# Sheet1.net
KiCad netlist of a schematic drawn in Altium Designer
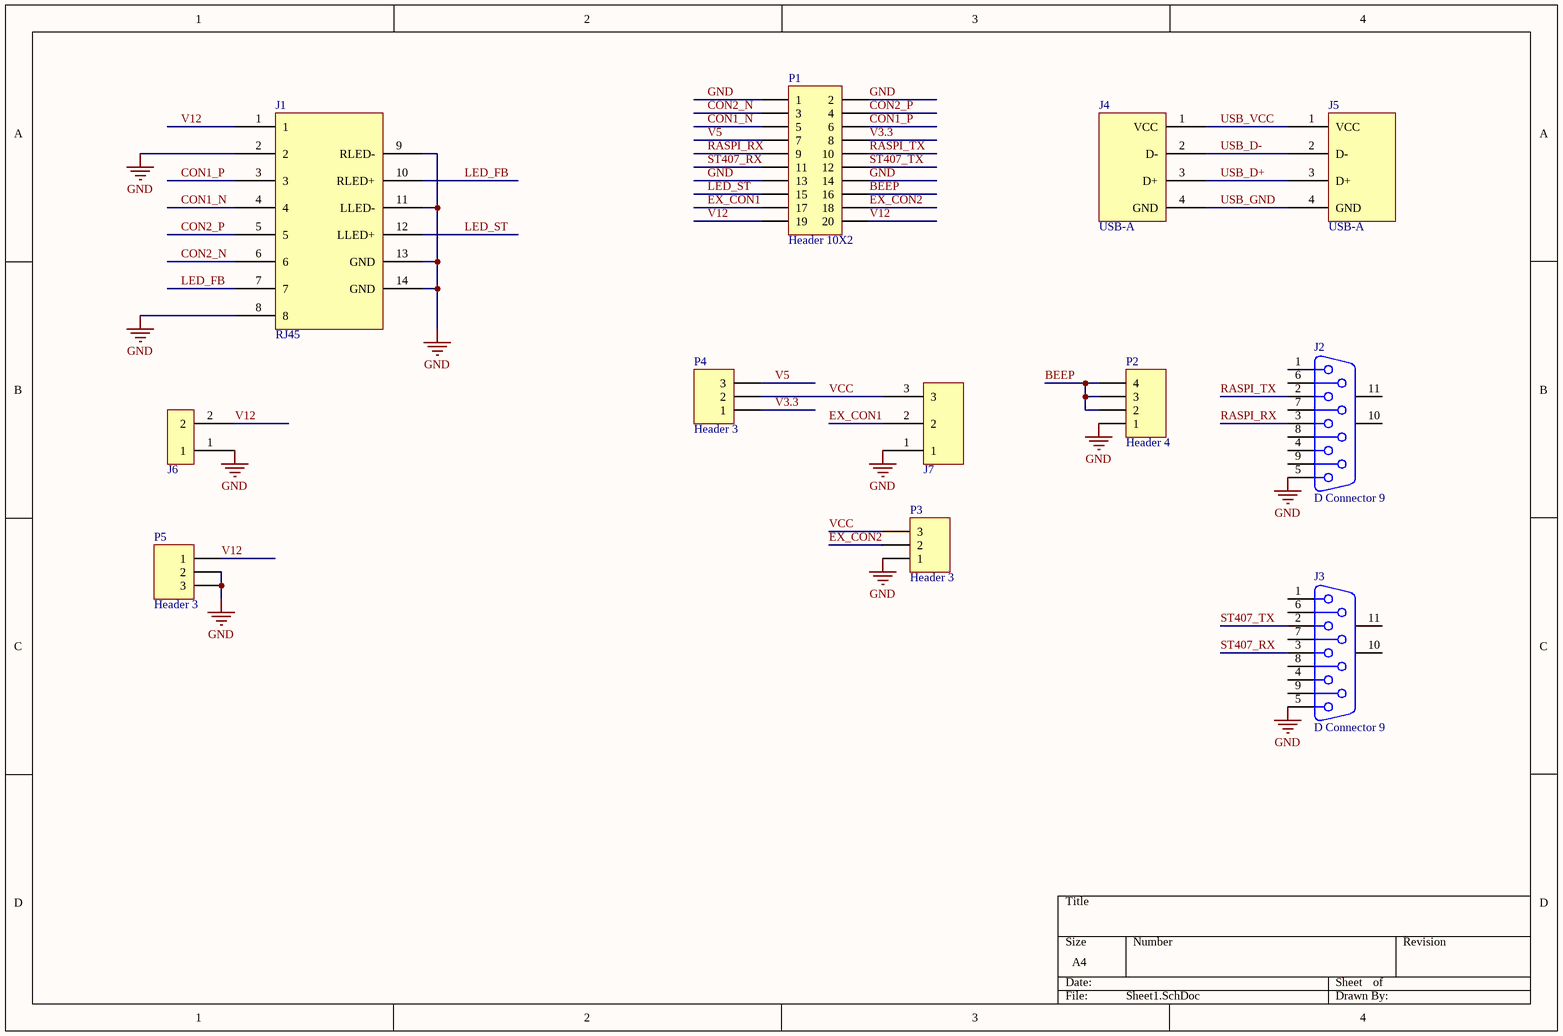
[diagram p0: Sheet1.SchDoc]

(export (version "E")
  (design (tool "Eeschema 10.0.6"))
  (components
    (comp (ref "J1") (value "RJ45") (footprint "RJ45_1") (libsource (lib "CHK-I") (part "RJ45_1")))
    (comp (ref "J2")
      (value "D Connector 9")
      (footprint "DSUB1.385-2H9")
      (description "Receptacle Assembly, 9 Position, Right Angle")
      (fields (field (name "PUBLISHER") "Altium Limited"))
      (libsource (lib "Miscellaneous Connectors") (part "D Connector 9"))
    )
    (comp (ref "J3")
      (value "D Connector 9")
      (footprint "DSUB1.385-2H9")
      (description "Receptacle Assembly, 9 Position, Right Angle")
      (fields (field (name "PUBLISHER") "Altium Limited"))
      (libsource (lib "Miscellaneous Connectors") (part "D Connector 9"))
    )
    (comp (ref "J4")
      (value "USB-A")
      (footprint "USB-A")
      (description "USB-A female")
      (libsource (lib "") (part "USB-A_1"))
    )
    (comp (ref "J5")
      (value "USB-A")
      (footprint "USB-A")
      (description "USB-A female")
      (libsource (lib "CHK-I") (part "USB-A"))
    )
    (comp (ref "J6") (value "XK7.62-2P") (footprint "XK7.62-2P") (libsource (lib "CHK-I") (part "XK7.62-2P")))
    (comp (ref "J7") (value "KF301-3P") (footprint "KF301-3P") (libsource (lib "CHK-I") (part "KF301-3P")))
    (comp (ref "P1")
      (value "Header 10X2")
      (footprint "HDR2X10")
      (description "Header, 10-Pin, Dual row")
      (fields (field (name "PUBLISHER") "Altium Limited"))
      (libsource (lib "Miscellaneous Connectors") (part "Header 10X2"))
    )
    (comp (ref "P2")
      (value "Header 4")
      (footprint "HDR1X4")
      (description "Header, 4-Pin")
      (fields (field (name "PUBLISHER") "Altium Limited"))
      (libsource (lib "Miscellaneous Connectors") (part "Header 4"))
    )
    (comp (ref "P3")
      (value "Header 3")
      (footprint "HDR1X3")
      (description "Header, 3-Pin")
      (fields (field (name "PUBLISHER") "Altium Limited"))
      (libsource (lib "Miscellaneous Connectors") (part "Header 3"))
    )
    (comp (ref "P4")
      (value "Header 3")
      (footprint "HDR1X3")
      (description "Header, 3-Pin")
      (fields (field (name "PUBLISHER") "Altium Limited"))
      (libsource (lib "") (part "Header 3_2"))
    )
    (comp (ref "P5")
      (value "Header 3")
      (footprint "DC005")
      (description "Header, 3-Pin")
      (fields (field (name "PUBLISHER") "Altium Limited"))
      (libsource (lib "") (part "Header 3_1"))
    )
  )
  (nets
    (net (code "1") (name "/BEEP") (class "Default")
      (node (ref "P1") (pin "16") (pinfunction "16_16") (pintype "passive"))
      (node (ref "P2") (pin "2") (pinfunction "2_2") (pintype "passive"))
      (node (ref "P2") (pin "3") (pinfunction "3_3") (pintype "passive"))
      (node (ref "P2") (pin "4") (pinfunction "4_4") (pintype "passive"))
    )
    (net (code "2") (name "/CON1_N") (class "Default")
      (node (ref "J1") (pin "4") (pinfunction "4_4") (pintype "passive"))
      (node (ref "P1") (pin "5") (pinfunction "5_5") (pintype "passive"))
    )
    (net (code "3") (name "/CON1_P") (class "Default")
      (node (ref "J1") (pin "3") (pinfunction "3_3") (pintype "passive"))
      (node (ref "P1") (pin "6") (pinfunction "6_6") (pintype "passive"))
    )
    (net (code "4") (name "/CON2_N") (class "Default")
      (node (ref "J1") (pin "6") (pinfunction "6_6") (pintype "passive"))
      (node (ref "P1") (pin "3") (pinfunction "3_3") (pintype "passive"))
    )
    (net (code "5") (name "/CON2_P") (class "Default")
      (node (ref "J1") (pin "5") (pinfunction "5_5") (pintype "passive"))
      (node (ref "P1") (pin "4") (pinfunction "4_4") (pintype "passive"))
    )
    (net (code "6") (name "/EX_CON1") (class "Default")
      (node (ref "J7") (pin "2") (pinfunction "2_2") (pintype "passive"))
      (node (ref "P1") (pin "17") (pinfunction "17_17") (pintype "passive"))
    )
    (net (code "7") (name "/EX_CON2") (class "Default")
      (node (ref "P1") (pin "18") (pinfunction "18_18") (pintype "passive"))
      (node (ref "P3") (pin "2") (pinfunction "2_2") (pintype "passive"))
    )
    (net (code "8") (name "/LED_FB") (class "Default")
      (node (ref "J1") (pin "10") (pinfunction "RLED+_10") (pintype "passive"))
      (node (ref "J1") (pin "7") (pinfunction "7_7") (pintype "passive"))
    )
    (net (code "9") (name "/LED_ST") (class "Default")
      (node (ref "J1") (pin "12") (pinfunction "LLED+_12") (pintype "passive"))
      (node (ref "P1") (pin "15") (pinfunction "15_15") (pintype "passive"))
    )
    (net (code "10") (name "/RASPI_RX") (class "Default")
      (node (ref "J2") (pin "3") (pinfunction "3_3") (pintype "passive"))
      (node (ref "P1") (pin "9") (pinfunction "9_9") (pintype "passive"))
    )
    (net (code "11") (name "/RASPI_TX") (class "Default")
      (node (ref "J2") (pin "2") (pinfunction "2_2") (pintype "passive"))
      (node (ref "P1") (pin "10") (pinfunction "10_10") (pintype "passive"))
    )
    (net (code "12") (name "/ST407_RX") (class "Default")
      (node (ref "J3") (pin "3") (pinfunction "3_3") (pintype "passive"))
      (node (ref "P1") (pin "11") (pinfunction "11_11") (pintype "passive"))
    )
    (net (code "13") (name "/ST407_TX") (class "Default")
      (node (ref "J3") (pin "2") (pinfunction "2_2") (pintype "passive"))
      (node (ref "P1") (pin "12") (pinfunction "12_12") (pintype "passive"))
    )
    (net (code "14") (name "/USB_D+") (class "Default")
      (node (ref "J4") (pin "3") (pinfunction "D+_3") (pintype "passive"))
      (node (ref "J5") (pin "3") (pinfunction "D+_3") (pintype "passive"))
    )
    (net (code "15") (name "/USB_D-") (class "Default")
      (node (ref "J4") (pin "2") (pinfunction "D-_2") (pintype "passive"))
      (node (ref "J5") (pin "2") (pinfunction "D-_2") (pintype "passive"))
    )
    (net (code "16") (name "/USB_GND") (class "Default")
      (node (ref "J4") (pin "4") (pinfunction "GND_4") (pintype "passive"))
      (node (ref "J5") (pin "4") (pinfunction "GND_4") (pintype "passive"))
    )
    (net (code "17") (name "/USB_VCC") (class "Default")
      (node (ref "J4") (pin "1") (pinfunction "VCC_1") (pintype "passive"))
      (node (ref "J5") (pin "1") (pinfunction "VCC_1") (pintype "passive"))
    )
    (net (code "18") (name "/V3.3") (class "Default")
      (node (ref "P1") (pin "8") (pinfunction "8_8") (pintype "passive"))
      (node (ref "P4") (pin "1") (pinfunction "1_1") (pintype "passive"))
    )
    (net (code "19") (name "/V5") (class "Default")
      (node (ref "P1") (pin "7") (pinfunction "7_7") (pintype "passive"))
      (node (ref "P4") (pin "3") (pinfunction "3_3") (pintype "passive"))
    )
    (net (code "20") (name "/V12") (class "Default")
      (node (ref "J1") (pin "1") (pinfunction "1_1") (pintype "passive"))
      (node (ref "J6") (pin "2") (pinfunction "2_2") (pintype "passive"))
      (node (ref "P1") (pin "19") (pinfunction "19_19") (pintype "passive"))
      (node (ref "P1") (pin "20") (pinfunction "20_20") (pintype "passive"))
      (node (ref "P5") (pin "1") (pinfunction "1_1") (pintype "passive"))
    )
    (net (code "21") (name "/VCC") (class "Default")
      (node (ref "J7") (pin "3") (pinfunction "3_3") (pintype "passive"))
      (node (ref "P3") (pin "3") (pinfunction "3_3") (pintype "passive"))
      (node (ref "P4") (pin "2") (pinfunction "2_2") (pintype "passive"))
    )
    (net (code "22") (name "GND") (class "Default")
      (node (ref "J1") (pin "11") (pinfunction "LLED-_11") (pintype "passive"))
      (node (ref "J1") (pin "13") (pinfunction "GND_13") (pintype "passive"))
      (node (ref "J1") (pin "14") (pinfunction "GND_14") (pintype "passive"))
      (node (ref "J1") (pin "2") (pinfunction "2_2") (pintype "passive"))
      (node (ref "J1") (pin "8") (pinfunction "8_8") (pintype "passive"))
      (node (ref "J1") (pin "9") (pinfunction "RLED-_9") (pintype "passive"))
      (node (ref "J2") (pin "5") (pinfunction "5_5") (pintype "passive"))
      (node (ref "J3") (pin "5") (pinfunction "5_5") (pintype "passive"))
      (node (ref "J6") (pin "1") (pinfunction "1_1") (pintype "passive"))
      (node (ref "J7") (pin "1") (pinfunction "1_1") (pintype "passive"))
      (node (ref "P1") (pin "1") (pinfunction "1_1") (pintype "passive"))
      (node (ref "P1") (pin "13") (pinfunction "13_13") (pintype "passive"))
      (node (ref "P1") (pin "14") (pinfunction "14_14") (pintype "passive"))
      (node (ref "P1") (pin "2") (pinfunction "2_2") (pintype "passive"))
      (node (ref "P2") (pin "1") (pinfunction "1_1") (pintype "passive"))
      (node (ref "P3") (pin "1") (pinfunction "1_1") (pintype "passive"))
      (node (ref "P5") (pin "2") (pinfunction "2_2") (pintype "passive"))
      (node (ref "P5") (pin "3") (pinfunction "3_3") (pintype "passive"))
    )
    (net (code "23") (name "unconnected-(J2-MH1-Pad10)") (class "Default")
      (node (ref "J2") (pin "10") (pinfunction "MH1_10") (pintype "passive"))
    )
    (net (code "24") (name "unconnected-(J2-MH2-Pad11)") (class "Default")
      (node (ref "J2") (pin "11") (pinfunction "MH2_11") (pintype "passive"))
    )
    (net (code "25") (name "unconnected-(J2-Pad1)") (class "Default")
      (node (ref "J2") (pin "1") (pinfunction "1_1") (pintype "passive"))
    )
    (net (code "26") (name "unconnected-(J2-Pad4)") (class "Default")
      (node (ref "J2") (pin "4") (pinfunction "4_4") (pintype "passive"))
    )
    (net (code "27") (name "unconnected-(J2-Pad6)") (class "Default")
      (node (ref "J2") (pin "6") (pinfunction "6_6") (pintype "passive"))
    )
    (net (code "28") (name "unconnected-(J2-Pad7)") (class "Default")
      (node (ref "J2") (pin "7") (pinfunction "7_7") (pintype "passive"))
    )
    (net (code "29") (name "unconnected-(J2-Pad8)") (class "Default")
      (node (ref "J2") (pin "8") (pinfunction "8_8") (pintype "passive"))
    )
    (net (code "30") (name "unconnected-(J2-Pad9)") (class "Default")
      (node (ref "J2") (pin "9") (pinfunction "9_9") (pintype "passive"))
    )
    (net (code "31") (name "unconnected-(J3-MH1-Pad10)") (class "Default")
      (node (ref "J3") (pin "10") (pinfunction "MH1_10") (pintype "passive"))
    )
    (net (code "32") (name "unconnected-(J3-MH2-Pad11)") (class "Default")
      (node (ref "J3") (pin "11") (pinfunction "MH2_11") (pintype "passive"))
    )
    (net (code "33") (name "unconnected-(J3-Pad1)") (class "Default")
      (node (ref "J3") (pin "1") (pinfunction "1_1") (pintype "passive"))
    )
    (net (code "34") (name "unconnected-(J3-Pad4)") (class "Default")
      (node (ref "J3") (pin "4") (pinfunction "4_4") (pintype "passive"))
    )
    (net (code "35") (name "unconnected-(J3-Pad6)") (class "Default")
      (node (ref "J3") (pin "6") (pinfunction "6_6") (pintype "passive"))
    )
    (net (code "36") (name "unconnected-(J3-Pad7)") (class "Default")
      (node (ref "J3") (pin "7") (pinfunction "7_7") (pintype "passive"))
    )
    (net (code "37") (name "unconnected-(J3-Pad8)") (class "Default")
      (node (ref "J3") (pin "8") (pinfunction "8_8") (pintype "passive"))
    )
    (net (code "38") (name "unconnected-(J3-Pad9)") (class "Default")
      (node (ref "J3") (pin "9") (pinfunction "9_9") (pintype "passive"))
    )
  )
)
